# dual_encoder_shield_3v_reve.net
KiCad netlist of a schematic drawn in EAGLE
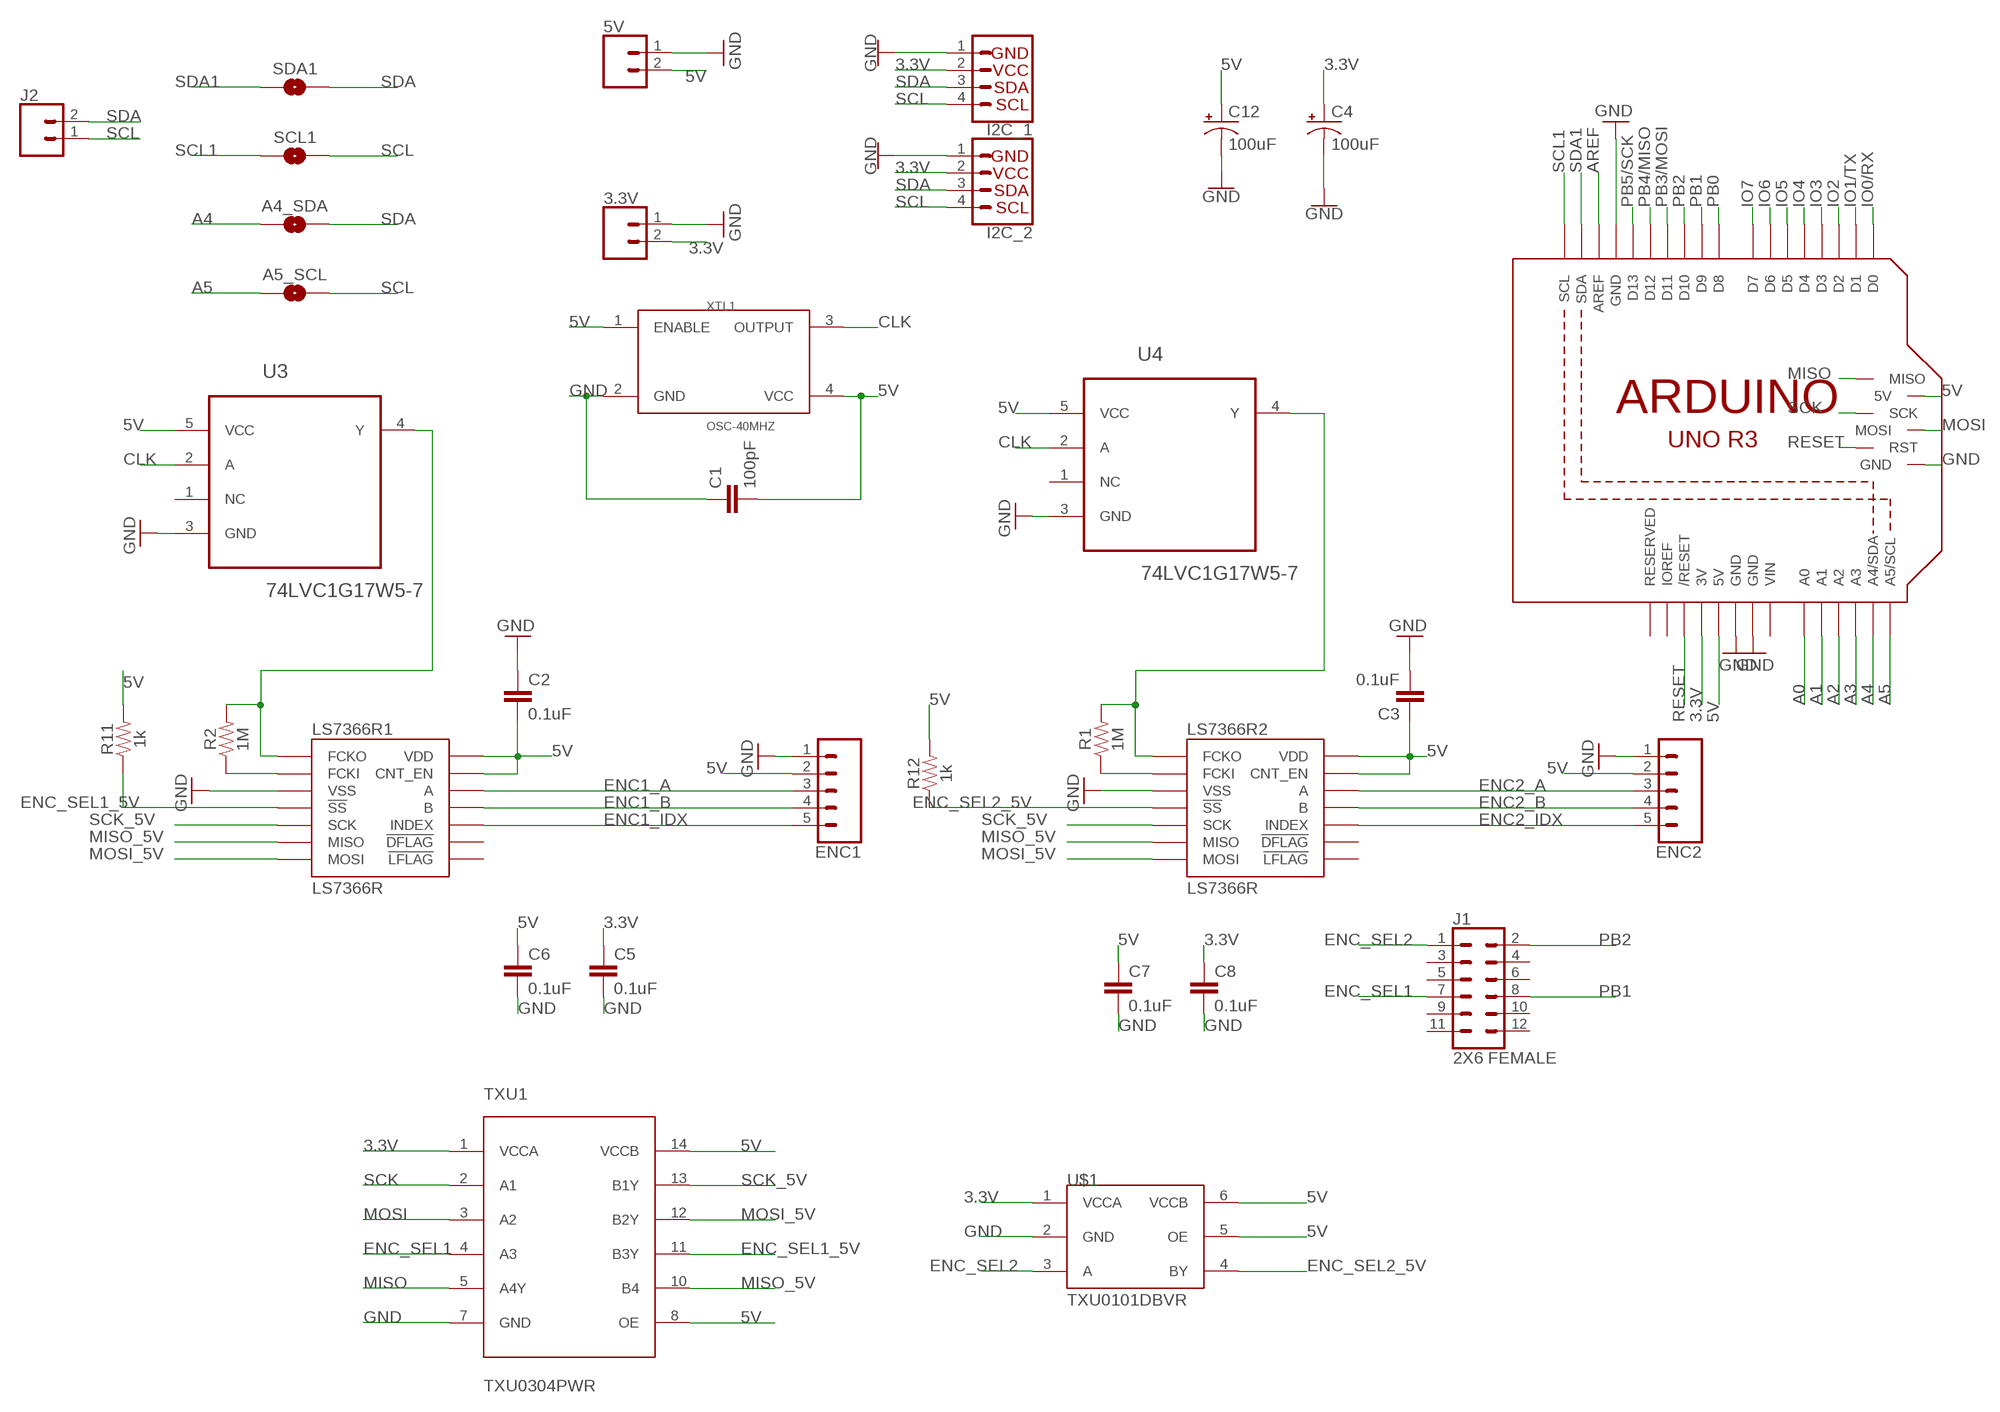
[diagram p0: schematic, sheet 1]

(export (version "E")
  (design (tool "Eeschema 10.0.6"))
  (components
    (comp (ref "3.3V")
      (value "CONN_02-JST-2MM-SMT")
      (footprint "eagle-import:JST-2-SMD")
      (libsource (lib "eagle-import") (part "CONN_02-JST-2MM-SMT"))
    )
    (comp (ref "5V")
      (value "CONN_02-JST-2MM-SMT")
      (footprint "eagle-import:JST-2-SMD")
      (libsource (lib "eagle-import") (part "CONN_02-JST-2MM-SMT"))
    )
    (comp (ref "A4_SDA")
      (value "JUMPER-SMT_2_NO_NO-SILK")
      (footprint "eagle-import:SMT-JUMPER_2_NO_NO-SILK")
      (libsource (lib "eagle-import") (part "JUMPER-SMT_2_NO_NO-SILK"))
    )
    (comp (ref "A5_SCL")
      (value "JUMPER-SMT_2_NO_NO-SILK")
      (footprint "eagle-import:SMT-JUMPER_2_NO_NO-SILK")
      (libsource (lib "eagle-import") (part "JUMPER-SMT_2_NO_NO-SILK"))
    )
    (comp (ref "C1")
      (value "100pF")
      (footprint "eagle-import:0603")
      (libsource (lib "eagle-import") (part "100PF-0603-50V-5%"))
    )
    (comp (ref "C2")
      (value "0.1uF")
      (footprint "eagle-import:0603")
      (libsource (lib "eagle-import") (part "0.1UF-0603-25V-5%"))
    )
    (comp (ref "C3")
      (value "0.1uF")
      (footprint "eagle-import:0603")
      (libsource (lib "eagle-import") (part "0.1UF-0603-25V-5%"))
    )
    (comp (ref "C4")
      (value "100uF")
      (footprint "eagle-import:PANASONIC_D")
      (libsource (lib "eagle-import") (part "100UF-POLAR-25V-20%(ELEC)"))
    )
    (comp (ref "C5")
      (value "0.1uF")
      (footprint "eagle-import:0603")
      (libsource (lib "eagle-import") (part "0.1UF-0603-25V-5%"))
    )
    (comp (ref "C6")
      (value "0.1uF")
      (footprint "eagle-import:0603")
      (libsource (lib "eagle-import") (part "0.1UF-0603-25V-5%"))
    )
    (comp (ref "C7")
      (value "0.1uF")
      (footprint "eagle-import:0603")
      (libsource (lib "eagle-import") (part "0.1UF-0603-25V-5%"))
    )
    (comp (ref "C8")
      (value "0.1uF")
      (footprint "eagle-import:0603")
      (libsource (lib "eagle-import") (part "0.1UF-0603-25V-5%"))
    )
    (comp (ref "C12")
      (value "100uF")
      (footprint "eagle-import:PANASONIC_D")
      (libsource (lib "eagle-import") (part "100UF-POLAR-25V-20%(ELEC)"))
    )
    (comp (ref "ENC1")
      (value "CONN_05")
      (footprint "eagle-import:1X05")
      (libsource (lib "eagle-import") (part "CONN_05"))
    )
    (comp (ref "ENC2")
      (value "CONN_05")
      (footprint "eagle-import:1X05")
      (libsource (lib "eagle-import") (part "CONN_05"))
    )
    (comp (ref "I2C_1")
      (value "QWIIC_CONNECTORJS-1MM")
      (footprint "eagle-import:JST04_1MM_RA")
      (libsource (lib "eagle-import") (part "QWIIC_CONNECTORJS-1MM"))
    )
    (comp (ref "I2C_2")
      (value "QWIIC_CONNECTORJS-1MM")
      (footprint "eagle-import:JST04_1MM_RA")
      (libsource (lib "eagle-import") (part "QWIIC_CONNECTORJS-1MM"))
    )
    (comp (ref "J1")
      (value "2X6 FEMALE")
      (footprint "eagle-import:2X6")
      (libsource (lib "eagle-import") (part "CONN_06X2PTH_FEMALE"))
    )
    (comp (ref "J2")
      (value "CONN_02")
      (footprint "eagle-import:1X02")
      (libsource (lib "eagle-import") (part "CONN_02"))
    )
    (comp (ref "LS7366R1")
      (value "LS7366R")
      (footprint "eagle-import:SOIC14")
      (fields (field (name "MF") "LSI"))
      (libsource (lib "eagle-import") (part "LS7366R"))
    )
    (comp (ref "LS7366R2")
      (value "LS7366R")
      (footprint "eagle-import:SOIC14")
      (fields (field (name "MF") "LSI"))
      (libsource (lib "eagle-import") (part "LS7366R"))
    )
    (comp (ref "M1")
      (value "ARDUINO_R3_ICSP")
      (footprint "eagle-import:ARDUINOR3_ICSP")
      (libsource (lib "eagle-import") (part "ARDUINO_R3_ICSP"))
    )
    (comp (ref "R1")
      (value "1M")
      (footprint "eagle-import:0603")
      (libsource (lib "eagle-import") (part "1MOHM-0603-1/4W-5%"))
    )
    (comp (ref "R2")
      (value "1M")
      (footprint "eagle-import:0603")
      (libsource (lib "eagle-import") (part "1MOHM-0603-1/4W-5%"))
    )
    (comp (ref "R11")
      (value "1k")
      (footprint "eagle-import:0603")
      (libsource (lib "eagle-import") (part "1KOHM-0603-1/10W-1%"))
    )
    (comp (ref "R12")
      (value "1k")
      (footprint "eagle-import:0603")
      (libsource (lib "eagle-import") (part "1KOHM-0603-1/10W-1%"))
    )
    (comp (ref "SCL1")
      (value "JUMPER-SMT_2_NO_NO-SILK")
      (footprint "eagle-import:SMT-JUMPER_2_NO_NO-SILK")
      (libsource (lib "eagle-import") (part "JUMPER-SMT_2_NO_NO-SILK"))
    )
    (comp (ref "SDA1")
      (value "JUMPER-SMT_2_NO_NO-SILK")
      (footprint "eagle-import:SMT-JUMPER_2_NO_NO-SILK")
      (libsource (lib "eagle-import") (part "JUMPER-SMT_2_NO_NO-SILK"))
    )
    (comp (ref "TXU1")
      (value "TXU0304PWR")
      (footprint "eagle-import:SOP65P640X95-14N")
      (libsource (lib "eagle-import") (part "TXU0304PWR"))
    )
    (comp (ref "U$1")
      (value "TXU0101DBVR")
      (footprint "eagle-import:SOT23-6")
      (libsource (lib "eagle-import") (part "TXU0101DBVR"))
    )
    (comp (ref "U3")
      (value "74LVC1G17W5-7")
      (footprint "eagle-import:SOT95P280X145-5N")
      (fields (field (name "DIGI-KEY_PART_NUMBER") "74LVC1G17W5-7TR-ND") (field (name "MF") "Diodes Inc."))
      (libsource (lib "eagle-import") (part "74LVC1G17W5-7"))
    )
    (comp (ref "U4")
      (value "74LVC1G17W5-7")
      (footprint "eagle-import:SOT95P280X145-5N")
      (fields (field (name "DIGI-KEY_PART_NUMBER") "74LVC1G17W5-7TR-ND") (field (name "MF") "Diodes Inc."))
      (libsource (lib "eagle-import") (part "74LVC1G17W5-7"))
    )
    (comp (ref "XTL1")
      (value "OSC-40MHZ")
      (footprint "eagle-import:OSC_CB3LV-5I-50M000000")
      (libsource (lib "eagle-import") (part "OSC-40MHZ"))
    )
  )
  (nets
    (net (code "1") (name "/3.3V") (class "Default")
      (node (ref "3.3V") (pin "2") (pinfunction "1_2") (pintype "passive"))
      (node (ref "C4") (pin "+") (pinfunction "+_+") (pintype "passive"))
      (node (ref "C5") (pin "1") (pinfunction "1_1") (pintype "passive"))
      (node (ref "C8") (pin "1") (pinfunction "1_1") (pintype "passive"))
      (node (ref "I2C_1") (pin "2") (pinfunction "2_2") (pintype "power_in"))
      (node (ref "I2C_2") (pin "2") (pinfunction "2_2") (pintype "power_in"))
      (node (ref "M1") (pin "3V") (pinfunction "3V_3V") (pintype "power_in"))
      (node (ref "TXU1") (pin "1") (pinfunction "VCCA_1") (pintype "bidirectional"))
      (node (ref "U$1") (pin "1") (pinfunction "VCCA_1") (pintype "bidirectional"))
    )
    (net (code "2") (name "/5V") (class "Default")
      (node (ref "5V") (pin "2") (pinfunction "1_2") (pintype "passive"))
      (node (ref "C1") (pin "2") (pinfunction "2_2") (pintype "passive"))
      (node (ref "C12") (pin "+") (pinfunction "+_+") (pintype "passive"))
      (node (ref "C2") (pin "2") (pinfunction "2_2") (pintype "passive"))
      (node (ref "C3") (pin "1") (pinfunction "1_1") (pintype "passive"))
      (node (ref "C6") (pin "1") (pinfunction "1_1") (pintype "passive"))
      (node (ref "C7") (pin "1") (pinfunction "1_1") (pintype "passive"))
      (node (ref "ENC1") (pin "2") (pinfunction "2_2") (pintype "passive"))
      (node (ref "ENC2") (pin "2") (pinfunction "2_2") (pintype "passive"))
      (node (ref "LS7366R1") (pin "13") (pinfunction "CNT_EN_13") (pintype "bidirectional"))
      (node (ref "LS7366R1") (pin "14") (pinfunction "VDD_14") (pintype "bidirectional"))
      (node (ref "LS7366R2") (pin "13") (pinfunction "CNT_EN_13") (pintype "bidirectional"))
      (node (ref "LS7366R2") (pin "14") (pinfunction "VDD_14") (pintype "bidirectional"))
      (node (ref "M1") (pin "5V") (pinfunction "5V_5V") (pintype "power_in"))
      (node (ref "M1") (pin "5V_ICSP") (pinfunction "5V_5V_ICSP") (pintype "passive"))
      (node (ref "R11") (pin "2") (pinfunction "2_2") (pintype "passive"))
      (node (ref "R12") (pin "2") (pinfunction "2_2") (pintype "passive"))
      (node (ref "TXU1") (pin "14") (pinfunction "VCCB_14") (pintype "bidirectional"))
      (node (ref "TXU1") (pin "8") (pinfunction "OE_8") (pintype "bidirectional"))
      (node (ref "U$1") (pin "5") (pinfunction "OE_5") (pintype "bidirectional"))
      (node (ref "U$1") (pin "6") (pinfunction "VCCB_6") (pintype "bidirectional"))
      (node (ref "U3") (pin "5") (pinfunction "VCC_5") (pintype "power_in"))
      (node (ref "U4") (pin "5") (pinfunction "VCC_5") (pintype "power_in"))
      (node (ref "XTL1") (pin "1") (pinfunction "ENABLE_1") (pintype "bidirectional"))
      (node (ref "XTL1") (pin "4") (pinfunction "VCC_4") (pintype "bidirectional"))
    )
    (net (code "3") (name "/A0") (class "Default")
      (node (ref "M1") (pin "A0") (pinfunction "A0_A0") (pintype "bidirectional"))
    )
    (net (code "4") (name "/A1") (class "Default")
      (node (ref "M1") (pin "A1") (pinfunction "A1_A1") (pintype "bidirectional"))
    )
    (net (code "5") (name "/A2") (class "Default")
      (node (ref "M1") (pin "A2") (pinfunction "A2_A2") (pintype "bidirectional"))
    )
    (net (code "6") (name "/A3") (class "Default")
      (node (ref "M1") (pin "A3") (pinfunction "A3_A3") (pintype "bidirectional"))
    )
    (net (code "7") (name "/A4") (class "Default")
      (node (ref "A4_SDA") (pin "1") (pinfunction "1_1") (pintype "passive"))
      (node (ref "M1") (pin "A4") (pinfunction "A4/SDA_A4") (pintype "bidirectional"))
    )
    (net (code "8") (name "/A5") (class "Default")
      (node (ref "A5_SCL") (pin "1") (pinfunction "1_1") (pintype "passive"))
      (node (ref "M1") (pin "A5") (pinfunction "A5/SCL_A5") (pintype "bidirectional"))
    )
    (net (code "9") (name "/AREF") (class "Default")
      (node (ref "M1") (pin "AREF") (pinfunction "AREF_AREF") (pintype "bidirectional"))
    )
    (net (code "10") (name "/CLK") (class "Default")
      (node (ref "U3") (pin "2") (pinfunction "A_2") (pintype "input"))
      (node (ref "U4") (pin "2") (pinfunction "A_2") (pintype "input"))
      (node (ref "XTL1") (pin "3") (pinfunction "OUTPUT_3") (pintype "bidirectional"))
    )
    (net (code "11") (name "/ENC1_A") (class "Default")
      (node (ref "ENC1") (pin "3") (pinfunction "3_3") (pintype "passive"))
      (node (ref "LS7366R1") (pin "12") (pinfunction "A_12") (pintype "bidirectional"))
    )
    (net (code "12") (name "/ENC1_B") (class "Default")
      (node (ref "ENC1") (pin "4") (pinfunction "4_4") (pintype "passive"))
      (node (ref "LS7366R1") (pin "11") (pinfunction "B_11") (pintype "bidirectional"))
    )
    (net (code "13") (name "/ENC1_IDX") (class "Default")
      (node (ref "ENC1") (pin "5") (pinfunction "5_5") (pintype "passive"))
      (node (ref "LS7366R1") (pin "10") (pinfunction "INDEX_10") (pintype "bidirectional"))
    )
    (net (code "14") (name "/ENC2_A") (class "Default")
      (node (ref "ENC2") (pin "3") (pinfunction "3_3") (pintype "passive"))
      (node (ref "LS7366R2") (pin "12") (pinfunction "A_12") (pintype "bidirectional"))
    )
    (net (code "15") (name "/ENC2_B") (class "Default")
      (node (ref "ENC2") (pin "4") (pinfunction "4_4") (pintype "passive"))
      (node (ref "LS7366R2") (pin "11") (pinfunction "B_11") (pintype "bidirectional"))
    )
    (net (code "16") (name "/ENC2_IDX") (class "Default")
      (node (ref "ENC2") (pin "5") (pinfunction "5_5") (pintype "passive"))
      (node (ref "LS7366R2") (pin "10") (pinfunction "INDEX_10") (pintype "bidirectional"))
    )
    (net (code "17") (name "/ENC_SEL1") (class "Default")
      (node (ref "J1") (pin "7") (pinfunction "7_7") (pintype "passive"))
      (node (ref "TXU1") (pin "4") (pinfunction "A3_4") (pintype "bidirectional"))
    )
    (net (code "18") (name "/ENC_SEL1_5V") (class "Default")
      (node (ref "LS7366R1") (pin "4") (pinfunction "~{SS}_4") (pintype "bidirectional"))
      (node (ref "R11") (pin "1") (pinfunction "1_1") (pintype "passive"))
      (node (ref "TXU1") (pin "11") (pinfunction "B3Y_11") (pintype "bidirectional"))
    )
    (net (code "19") (name "/ENC_SEL2") (class "Default")
      (node (ref "J1") (pin "1") (pinfunction "1_1") (pintype "passive"))
      (node (ref "U$1") (pin "3") (pinfunction "A_3") (pintype "bidirectional"))
    )
    (net (code "20") (name "/ENC_SEL2_5V") (class "Default")
      (node (ref "LS7366R2") (pin "4") (pinfunction "~{SS}_4") (pintype "bidirectional"))
      (node (ref "R12") (pin "1") (pinfunction "1_1") (pintype "passive"))
      (node (ref "U$1") (pin "4") (pinfunction "BY_4") (pintype "bidirectional"))
    )
    (net (code "21") (name "/IO0{slash}RX") (class "Default")
      (node (ref "M1") (pin "D0") (pinfunction "D0_D0") (pintype "bidirectional"))
    )
    (net (code "22") (name "/IO1{slash}TX") (class "Default")
      (node (ref "M1") (pin "D1") (pinfunction "D1_D1") (pintype "bidirectional"))
    )
    (net (code "23") (name "/IO2") (class "Default")
      (node (ref "M1") (pin "D2") (pinfunction "D2_D2") (pintype "bidirectional"))
    )
    (net (code "24") (name "/IO3") (class "Default")
      (node (ref "M1") (pin "D3") (pinfunction "D3_D3") (pintype "bidirectional"))
    )
    (net (code "25") (name "/IO4") (class "Default")
      (node (ref "M1") (pin "D4") (pinfunction "D4_D4") (pintype "bidirectional"))
    )
    (net (code "26") (name "/IO5") (class "Default")
      (node (ref "M1") (pin "D5") (pinfunction "D5_D5") (pintype "bidirectional"))
    )
    (net (code "27") (name "/IO6") (class "Default")
      (node (ref "M1") (pin "D6") (pinfunction "D6_D6") (pintype "bidirectional"))
    )
    (net (code "28") (name "/IO7") (class "Default")
      (node (ref "M1") (pin "D7") (pinfunction "D7_D7") (pintype "bidirectional"))
    )
    (net (code "29") (name "/MISO") (class "Default")
      (node (ref "M1") (pin "MISO") (pinfunction "MISO_MISO") (pintype "passive"))
      (node (ref "TXU1") (pin "5") (pinfunction "A4Y_5") (pintype "bidirectional"))
    )
    (net (code "30") (name "/MISO_5V") (class "Default")
      (node (ref "LS7366R1") (pin "6") (pinfunction "MISO_6") (pintype "bidirectional"))
      (node (ref "LS7366R2") (pin "6") (pinfunction "MISO_6") (pintype "bidirectional"))
      (node (ref "TXU1") (pin "10") (pinfunction "B4_10") (pintype "bidirectional"))
    )
    (net (code "31") (name "/MOSI") (class "Default")
      (node (ref "M1") (pin "MOSI") (pinfunction "MOSI_MOSI") (pintype "passive"))
      (node (ref "TXU1") (pin "3") (pinfunction "A2_3") (pintype "bidirectional"))
    )
    (net (code "32") (name "/MOSI_5V") (class "Default")
      (node (ref "LS7366R1") (pin "7") (pinfunction "MOSI_7") (pintype "bidirectional"))
      (node (ref "LS7366R2") (pin "7") (pinfunction "MOSI_7") (pintype "bidirectional"))
      (node (ref "TXU1") (pin "12") (pinfunction "B2Y_12") (pintype "bidirectional"))
    )
    (net (code "33") (name "/PB0") (class "Default")
      (node (ref "M1") (pin "D8") (pinfunction "D8_D8") (pintype "bidirectional"))
    )
    (net (code "34") (name "/PB1") (class "Default")
      (node (ref "J1") (pin "8") (pinfunction "8_8") (pintype "passive"))
      (node (ref "M1") (pin "D9") (pinfunction "D9_D9") (pintype "bidirectional"))
    )
    (net (code "35") (name "/PB2") (class "Default")
      (node (ref "J1") (pin "2") (pinfunction "2_2") (pintype "passive"))
      (node (ref "M1") (pin "D10") (pinfunction "D10_D10") (pintype "bidirectional"))
    )
    (net (code "36") (name "/PB3{slash}MOSI") (class "Default")
      (node (ref "M1") (pin "D11") (pinfunction "D11_D11") (pintype "bidirectional"))
    )
    (net (code "37") (name "/PB4{slash}MISO") (class "Default")
      (node (ref "M1") (pin "D12") (pinfunction "D12_D12") (pintype "bidirectional"))
    )
    (net (code "38") (name "/PB5{slash}SCK") (class "Default")
      (node (ref "M1") (pin "D13") (pinfunction "D13_D13") (pintype "bidirectional"))
    )
    (net (code "39") (name "/RESET") (class "Default")
      (node (ref "M1") (pin "RESET") (pinfunction "/RESET_RESET") (pintype "bidirectional"))
      (node (ref "M1") (pin "RESET_ICSP") (pinfunction "RST_RESET_ICSP") (pintype "passive"))
    )
    (net (code "40") (name "/SCK") (class "Default")
      (node (ref "M1") (pin "SCK") (pinfunction "SCK_SCK") (pintype "passive"))
      (node (ref "TXU1") (pin "2") (pinfunction "A1_2") (pintype "bidirectional"))
    )
    (net (code "41") (name "/SCK_5V") (class "Default")
      (node (ref "LS7366R1") (pin "5") (pinfunction "SCK_5") (pintype "bidirectional"))
      (node (ref "LS7366R2") (pin "5") (pinfunction "SCK_5") (pintype "bidirectional"))
      (node (ref "TXU1") (pin "13") (pinfunction "B1Y_13") (pintype "bidirectional"))
    )
    (net (code "42") (name "/SCL") (class "Default")
      (node (ref "A5_SCL") (pin "2") (pinfunction "2_2") (pintype "passive"))
      (node (ref "I2C_1") (pin "4") (pinfunction "4_4") (pintype "passive"))
      (node (ref "I2C_2") (pin "4") (pinfunction "4_4") (pintype "passive"))
      (node (ref "J2") (pin "1") (pinfunction "1_1") (pintype "passive"))
      (node (ref "SCL1") (pin "2") (pinfunction "2_2") (pintype "passive"))
    )
    (net (code "43") (name "/SCL1") (class "Default")
      (node (ref "M1") (pin "SCL") (pinfunction "SCL_SCL") (pintype "bidirectional"))
      (node (ref "SCL1") (pin "1") (pinfunction "1_1") (pintype "passive"))
    )
    (net (code "44") (name "/SDA") (class "Default")
      (node (ref "A4_SDA") (pin "2") (pinfunction "2_2") (pintype "passive"))
      (node (ref "I2C_1") (pin "3") (pinfunction "3_3") (pintype "passive"))
      (node (ref "I2C_2") (pin "3") (pinfunction "3_3") (pintype "passive"))
      (node (ref "J2") (pin "2") (pinfunction "2_2") (pintype "passive"))
      (node (ref "SDA1") (pin "2") (pinfunction "2_2") (pintype "passive"))
    )
    (net (code "45") (name "/SDA1") (class "Default")
      (node (ref "M1") (pin "SDA") (pinfunction "SDA_SDA") (pintype "bidirectional"))
      (node (ref "SDA1") (pin "1") (pinfunction "1_1") (pintype "passive"))
    )
    (net (code "46") (name "/VIN") (class "Default")
      (node (ref "M1") (pin "VIN") (pinfunction "VIN_VIN") (pintype "power_in"))
    )
    (net (code "47") (name "GND") (class "Default")
      (node (ref "3.3V") (pin "1") (pinfunction "2_1") (pintype "passive"))
      (node (ref "5V") (pin "1") (pinfunction "2_1") (pintype "passive"))
      (node (ref "C1") (pin "1") (pinfunction "1_1") (pintype "passive"))
      (node (ref "C12") (pin "-") (pinfunction "-_-") (pintype "passive"))
      (node (ref "C2") (pin "1") (pinfunction "1_1") (pintype "passive"))
      (node (ref "C3") (pin "2") (pinfunction "2_2") (pintype "passive"))
      (node (ref "C4") (pin "-") (pinfunction "-_-") (pintype "passive"))
      (node (ref "C5") (pin "2") (pinfunction "2_2") (pintype "passive"))
      (node (ref "C6") (pin "2") (pinfunction "2_2") (pintype "passive"))
      (node (ref "C7") (pin "2") (pinfunction "2_2") (pintype "passive"))
      (node (ref "C8") (pin "2") (pinfunction "2_2") (pintype "passive"))
      (node (ref "ENC1") (pin "1") (pinfunction "1_1") (pintype "passive"))
      (node (ref "ENC2") (pin "1") (pinfunction "1_1") (pintype "passive"))
      (node (ref "I2C_1") (pin "1") (pinfunction "1_1") (pintype "power_in"))
      (node (ref "I2C_2") (pin "1") (pinfunction "1_1") (pintype "power_in"))
      (node (ref "LS7366R1") (pin "3") (pinfunction "VSS_3") (pintype "bidirectional"))
      (node (ref "LS7366R2") (pin "3") (pinfunction "VSS_3") (pintype "bidirectional"))
      (node (ref "M1") (pin "GND") (pinfunction "GND_GND") (pintype "power_in"))
      (node (ref "M1") (pin "GND@1") (pinfunction "GND_GND@1") (pintype "power_in"))
      (node (ref "M1") (pin "GND@2") (pinfunction "GND_GND@2") (pintype "passive"))
      (node (ref "M1") (pin "GND@3") (pinfunction "GND_GND@3") (pintype "power_in"))
      (node (ref "TXU1") (pin "7") (pinfunction "GND_7") (pintype "bidirectional"))
      (node (ref "U$1") (pin "2") (pinfunction "GND_2") (pintype "bidirectional"))
      (node (ref "U3") (pin "3") (pinfunction "GND_3") (pintype "passive"))
      (node (ref "U4") (pin "3") (pinfunction "GND_3") (pintype "passive"))
      (node (ref "XTL1") (pin "2") (pinfunction "GND_2") (pintype "bidirectional"))
    )
    (net (code "48") (name "Net-(LS7366R1-FCKI)") (class "Default")
      (node (ref "LS7366R1") (pin "2") (pinfunction "FCKI_2") (pintype "bidirectional"))
      (node (ref "R2") (pin "1") (pinfunction "1_1") (pintype "passive"))
    )
    (net (code "49") (name "Net-(LS7366R1-FCKO)") (class "Default")
      (node (ref "LS7366R1") (pin "1") (pinfunction "FCKO_1") (pintype "bidirectional"))
      (node (ref "R2") (pin "2") (pinfunction "2_2") (pintype "passive"))
      (node (ref "U3") (pin "4") (pinfunction "Y_4") (pintype "output"))
    )
    (net (code "50") (name "Net-(LS7366R2-FCKI)") (class "Default")
      (node (ref "LS7366R2") (pin "2") (pinfunction "FCKI_2") (pintype "bidirectional"))
      (node (ref "R1") (pin "1") (pinfunction "1_1") (pintype "passive"))
    )
    (net (code "51") (name "Net-(LS7366R2-FCKO)") (class "Default")
      (node (ref "LS7366R2") (pin "1") (pinfunction "FCKO_1") (pintype "bidirectional"))
      (node (ref "R1") (pin "2") (pinfunction "2_2") (pintype "passive"))
      (node (ref "U4") (pin "4") (pinfunction "Y_4") (pintype "output"))
    )
    (net (code "52") (name "unconnected-(J1-Pad3)") (class "Default")
      (node (ref "J1") (pin "3") (pinfunction "3_3") (pintype "passive"))
    )
    (net (code "53") (name "unconnected-(J1-Pad4)") (class "Default")
      (node (ref "J1") (pin "4") (pinfunction "4_4") (pintype "passive"))
    )
    (net (code "54") (name "unconnected-(J1-Pad5)") (class "Default")
      (node (ref "J1") (pin "5") (pinfunction "5_5") (pintype "passive"))
    )
    (net (code "55") (name "unconnected-(J1-Pad6)") (class "Default")
      (node (ref "J1") (pin "6") (pinfunction "6_6") (pintype "passive"))
    )
    (net (code "56") (name "unconnected-(J1-Pad9)") (class "Default")
      (node (ref "J1") (pin "9") (pinfunction "9_9") (pintype "passive"))
    )
    (net (code "57") (name "unconnected-(J1-Pad10)") (class "Default")
      (node (ref "J1") (pin "10") (pinfunction "10_10") (pintype "passive"))
    )
    (net (code "58") (name "unconnected-(J1-Pad11)") (class "Default")
      (node (ref "J1") (pin "11") (pinfunction "11_11") (pintype "passive"))
    )
    (net (code "59") (name "unconnected-(J1-Pad12)") (class "Default")
      (node (ref "J1") (pin "12") (pinfunction "12_12") (pintype "passive"))
    )
    (net (code "60") (name "unconnected-(LS7366R1-~{DFLAG}-Pad9)") (class "Default")
      (node (ref "LS7366R1") (pin "9") (pinfunction "~{DFLAG}_9") (pintype "bidirectional"))
    )
    (net (code "61") (name "unconnected-(LS7366R1-~{LFLAG}-Pad8)") (class "Default")
      (node (ref "LS7366R1") (pin "8") (pinfunction "~{LFLAG}_8") (pintype "bidirectional"))
    )
    (net (code "62") (name "unconnected-(LS7366R2-~{DFLAG}-Pad9)") (class "Default")
      (node (ref "LS7366R2") (pin "9") (pinfunction "~{DFLAG}_9") (pintype "bidirectional"))
    )
    (net (code "63") (name "unconnected-(LS7366R2-~{LFLAG}-Pad8)") (class "Default")
      (node (ref "LS7366R2") (pin "8") (pinfunction "~{LFLAG}_8") (pintype "bidirectional"))
    )
    (net (code "64") (name "unconnected-(M1-PadIOREF)") (class "Default")
      (node (ref "M1") (pin "IOREF") (pinfunction "IOREF_IOREF") (pintype "output"))
    )
    (net (code "65") (name "unconnected-(M1-PadRESERVED)") (class "Default")
      (node (ref "M1") (pin "RESERVED") (pinfunction "RESERVED_RESERVED") (pintype "no_connect"))
    )
    (net (code "66") (name "unconnected-(U3-NC-Pad1)") (class "Default")
      (node (ref "U3") (pin "1") (pinfunction "NC_1") (pintype "no_connect"))
    )
    (net (code "67") (name "unconnected-(U4-NC-Pad1)") (class "Default")
      (node (ref "U4") (pin "1") (pinfunction "NC_1") (pintype "no_connect"))
    )
  )
)
